# due-levelconverter.net
KiCad netlist of a schematic drawn in EAGLE
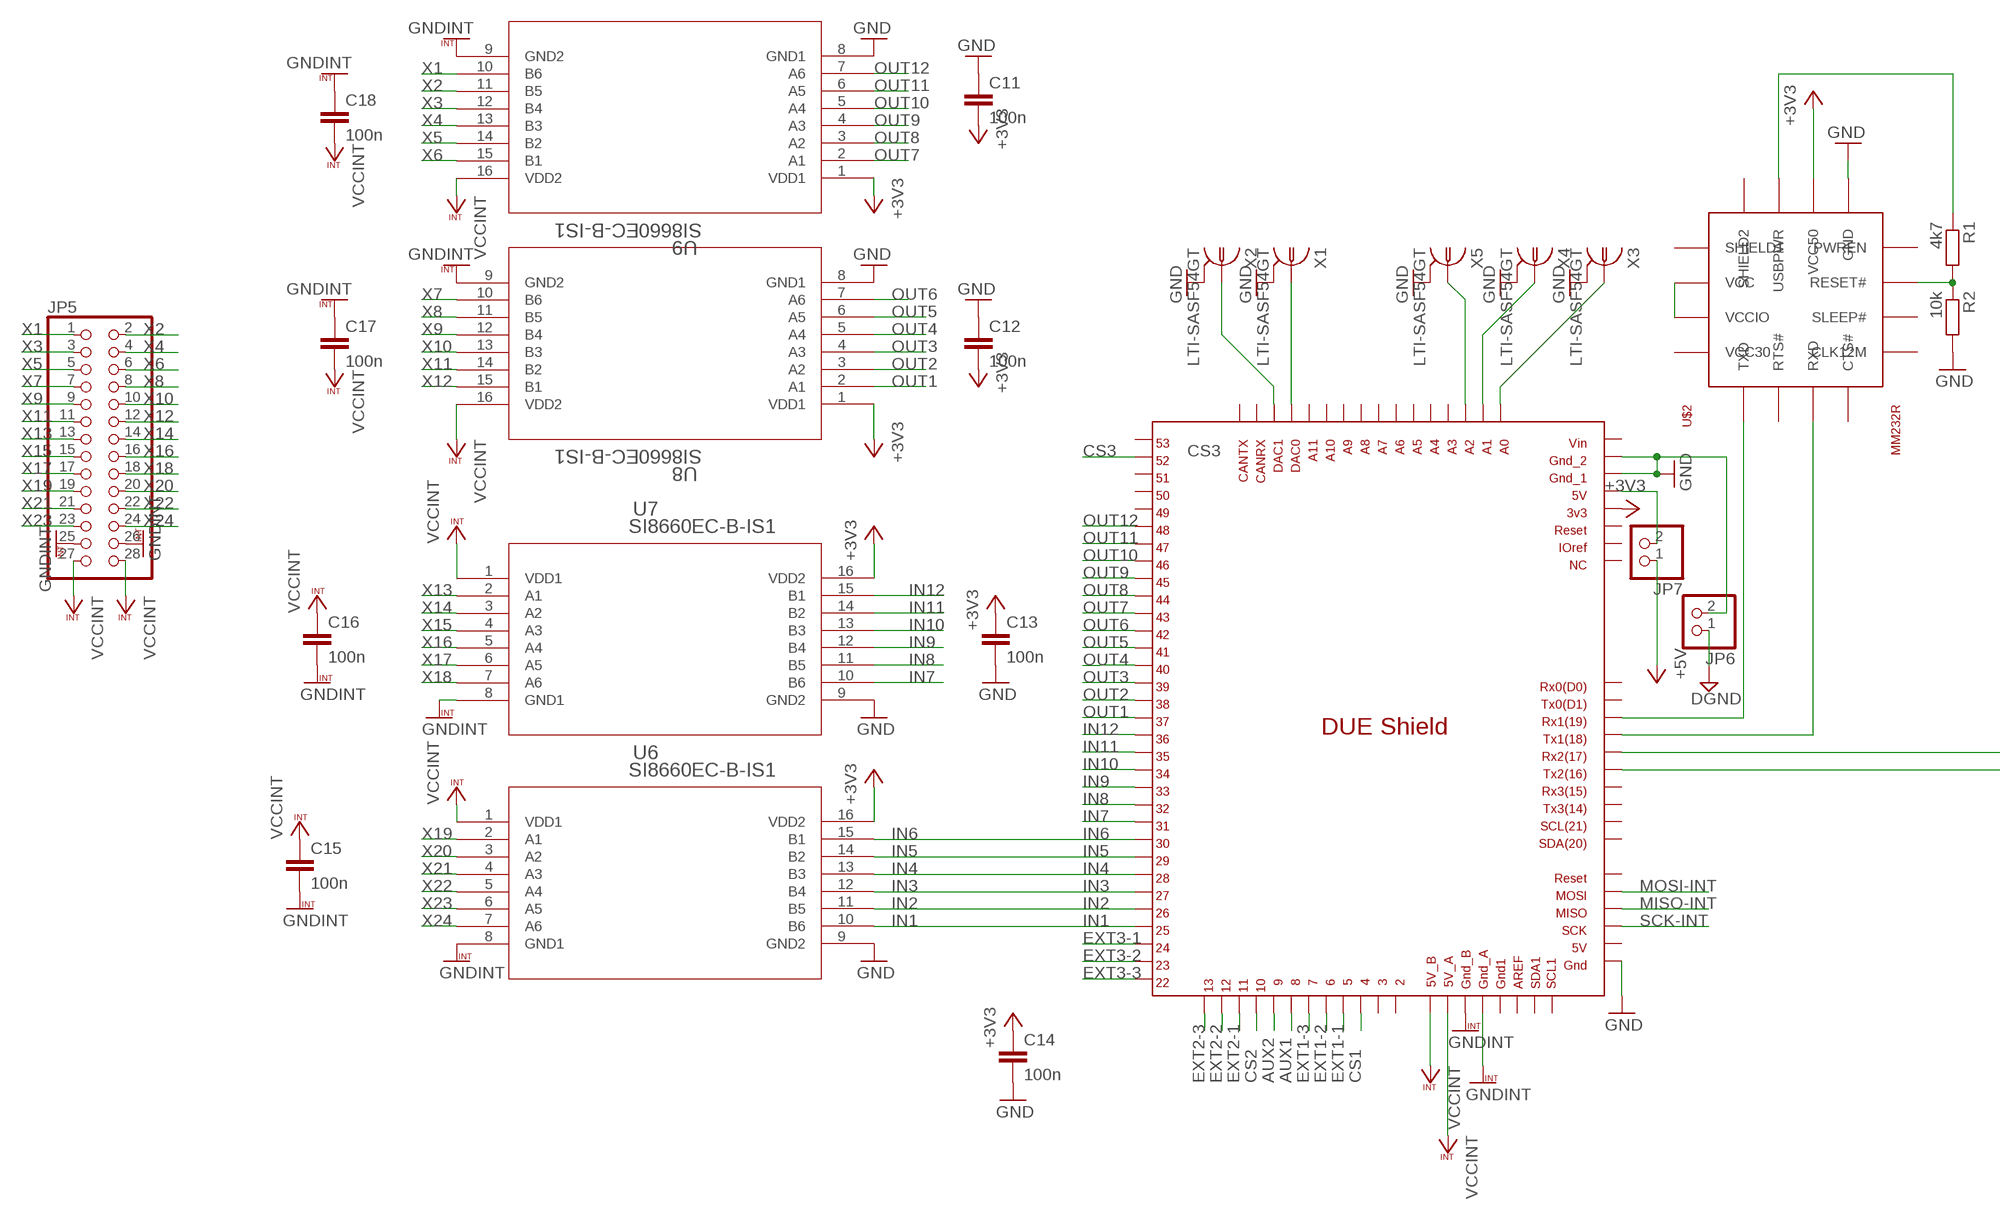
[diagram p0: schematic, sheet 1, part 1 of 2]
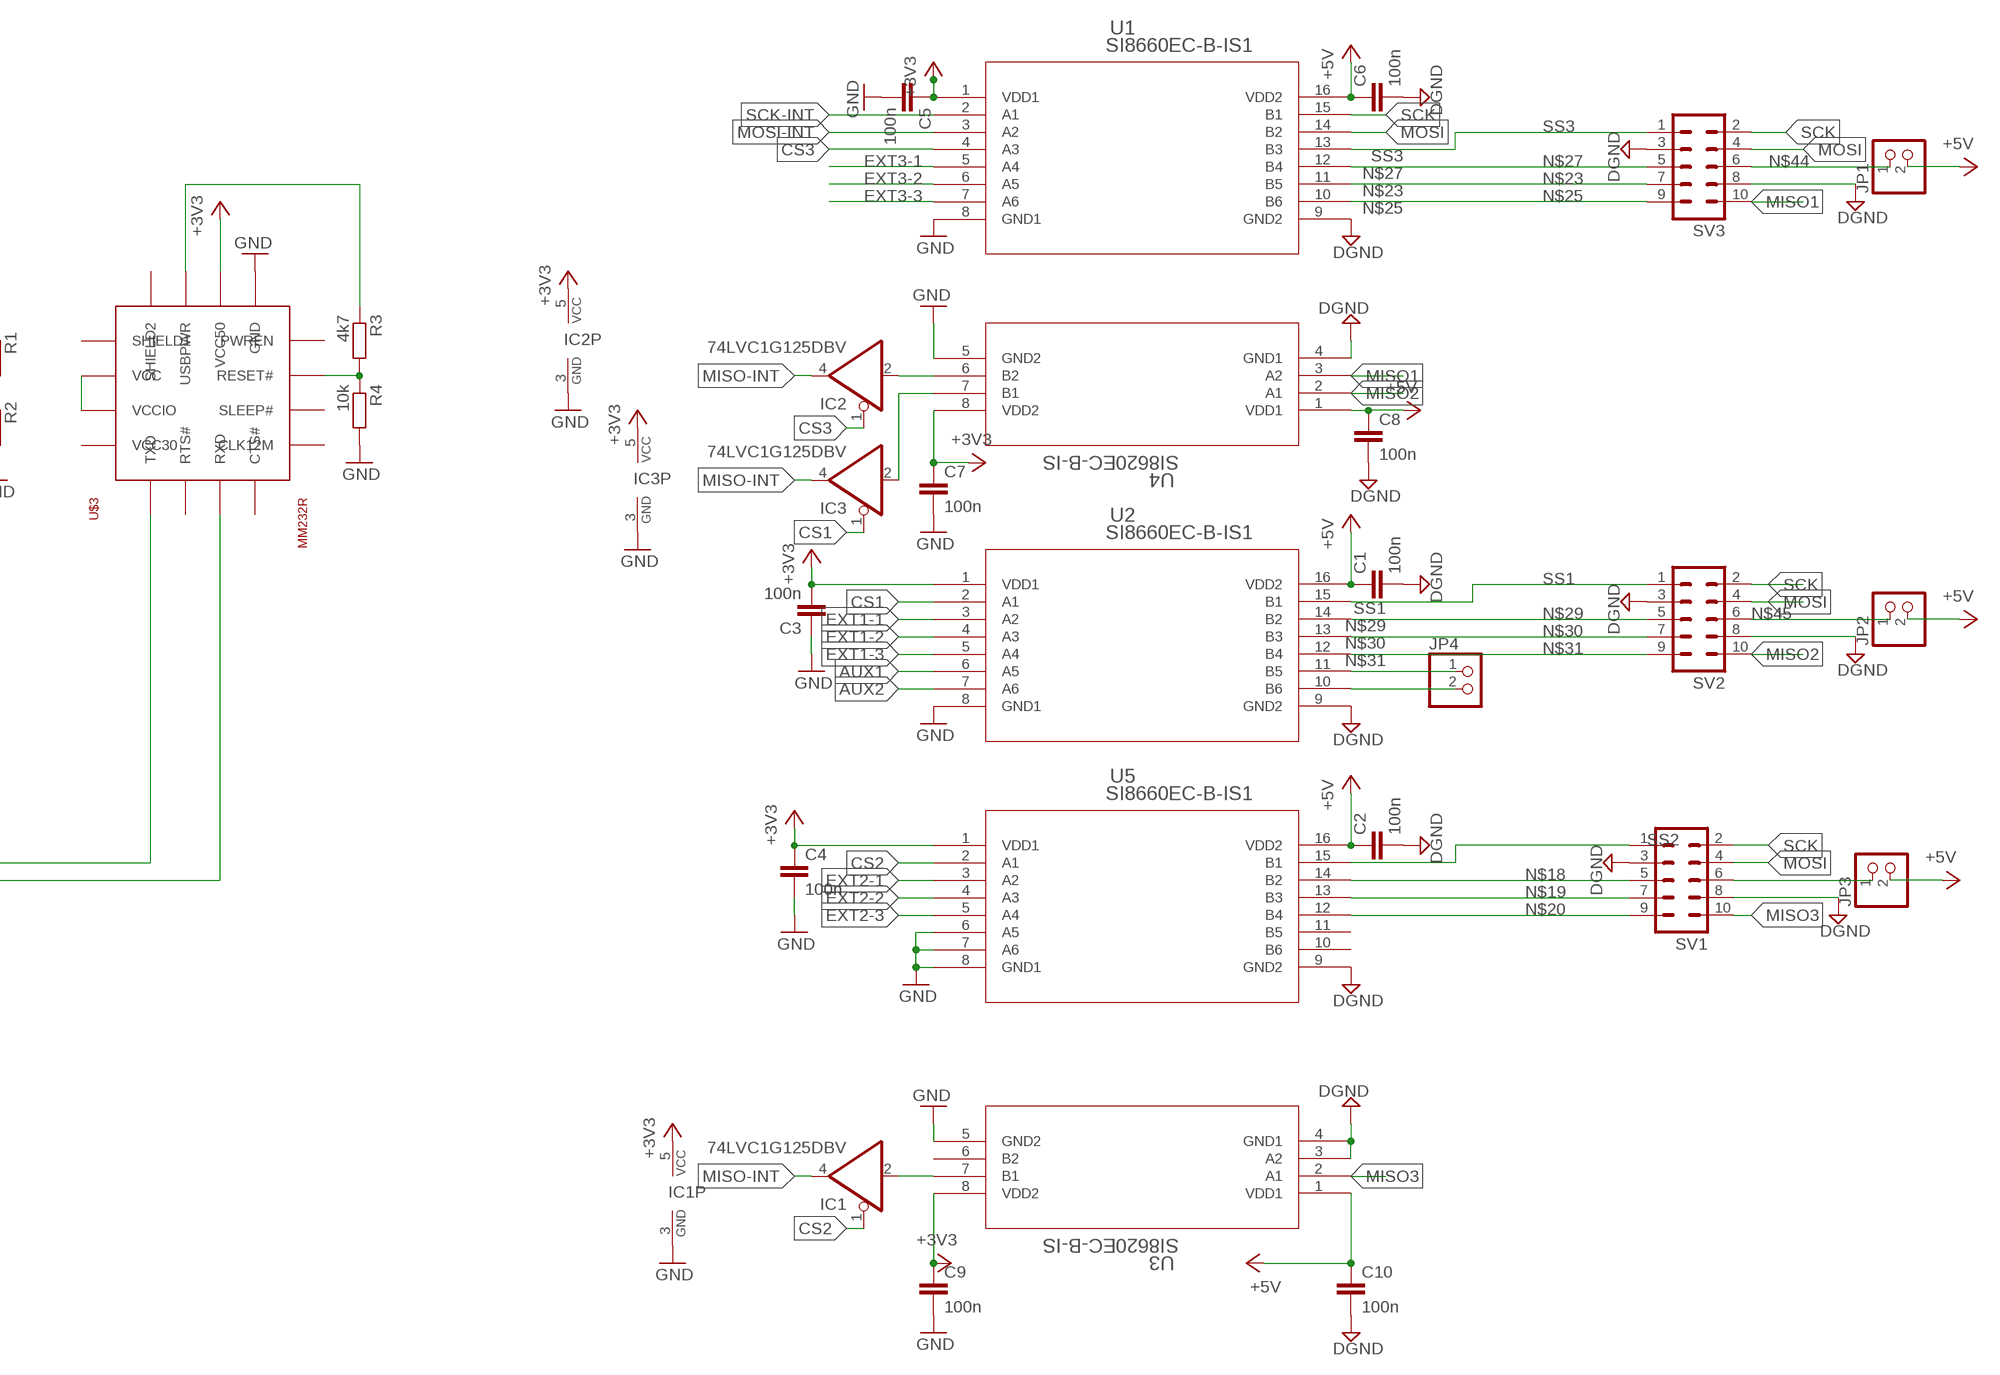
[diagram p1: schematic, sheet 1, part 2 of 2]

(export (version "E")
  (design (tool "Eeschema 10.0.6"))
  (components
    (comp (ref "C1")
      (value "100n")
      (footprint "eagle-import:C0805")
      (libsource (lib "eagle-import") (part "C-EUC0805"))
    )
    (comp (ref "C2")
      (value "100n")
      (footprint "eagle-import:C0805")
      (libsource (lib "eagle-import") (part "C-EUC0805"))
    )
    (comp (ref "C3")
      (value "100n")
      (footprint "eagle-import:C0805")
      (libsource (lib "eagle-import") (part "C-EUC0805"))
    )
    (comp (ref "C4")
      (value "100n")
      (footprint "eagle-import:C0805")
      (libsource (lib "eagle-import") (part "C-EUC0805"))
    )
    (comp (ref "C5")
      (value "100n")
      (footprint "eagle-import:C0805")
      (libsource (lib "eagle-import") (part "C-EUC0805"))
    )
    (comp (ref "C6")
      (value "100n")
      (footprint "eagle-import:C0805")
      (libsource (lib "eagle-import") (part "C-EUC0805"))
    )
    (comp (ref "C7")
      (value "100n")
      (footprint "eagle-import:C0805")
      (libsource (lib "eagle-import") (part "C-EUC0805"))
    )
    (comp (ref "C8")
      (value "100n")
      (footprint "eagle-import:C0805")
      (libsource (lib "eagle-import") (part "C-EUC0805"))
    )
    (comp (ref "C9")
      (value "100n")
      (footprint "eagle-import:C0805")
      (libsource (lib "eagle-import") (part "C-EUC0805"))
    )
    (comp (ref "C10")
      (value "100n")
      (footprint "eagle-import:C0805")
      (libsource (lib "eagle-import") (part "C-EUC0805"))
    )
    (comp (ref "C11")
      (value "100n")
      (footprint "eagle-import:C0805")
      (libsource (lib "eagle-import") (part "C-EUC0805"))
    )
    (comp (ref "C12")
      (value "100n")
      (footprint "eagle-import:C0805")
      (libsource (lib "eagle-import") (part "C-EUC0805"))
    )
    (comp (ref "C13")
      (value "100n")
      (footprint "eagle-import:C0805")
      (libsource (lib "eagle-import") (part "C-EUC0805"))
    )
    (comp (ref "C14")
      (value "100n")
      (footprint "eagle-import:C0805")
      (libsource (lib "eagle-import") (part "C-EUC0805"))
    )
    (comp (ref "C15")
      (value "100n")
      (footprint "eagle-import:C0805")
      (libsource (lib "eagle-import") (part "C-EUC0805"))
    )
    (comp (ref "C16")
      (value "100n")
      (footprint "eagle-import:C0805")
      (libsource (lib "eagle-import") (part "C-EUC0805"))
    )
    (comp (ref "C17")
      (value "100n")
      (footprint "eagle-import:C0805")
      (libsource (lib "eagle-import") (part "C-EUC0805"))
    )
    (comp (ref "C18")
      (value "100n")
      (footprint "eagle-import:C0805")
      (libsource (lib "eagle-import") (part "C-EUC0805"))
    )
    (comp (ref "IC1")
      (value "74LVC1G125DBV")
      (footprint "eagle-import:SOT23-5")
      (libsource (lib "eagle-import") (part "741G125DBVLVC"))
    )
    (comp (ref "IC2")
      (value "74LVC1G125DBV")
      (footprint "eagle-import:SOT23-5")
      (libsource (lib "eagle-import") (part "741G125DBVLVC"))
    )
    (comp (ref "IC3")
      (value "74LVC1G125DBV")
      (footprint "eagle-import:SOT23-5")
      (libsource (lib "eagle-import") (part "741G125DBVLVC"))
    )
    (comp (ref "JP1")
      (value "PINHD-1X2")
      (footprint "eagle-import:1X02")
      (libsource (lib "eagle-import") (part "PINHD-1X2"))
    )
    (comp (ref "JP2")
      (value "PINHD-1X2")
      (footprint "eagle-import:1X02")
      (libsource (lib "eagle-import") (part "PINHD-1X2"))
    )
    (comp (ref "JP3")
      (value "PINHD-1X2")
      (footprint "eagle-import:1X02")
      (libsource (lib "eagle-import") (part "PINHD-1X2"))
    )
    (comp (ref "JP4")
      (value "PINHD-1X2")
      (footprint "eagle-import:1X02")
      (libsource (lib "eagle-import") (part "PINHD-1X2"))
    )
    (comp (ref "JP5")
      (value "PINHD-2X14")
      (footprint "eagle-import:2X14")
      (libsource (lib "eagle-import") (part "PINHD-2X14"))
    )
    (comp (ref "JP6")
      (value "PINHD-1X2")
      (footprint "eagle-import:1X02")
      (libsource (lib "eagle-import") (part "PINHD-1X2"))
    )
    (comp (ref "JP7")
      (value "PINHD-1X2")
      (footprint "eagle-import:1X02")
      (libsource (lib "eagle-import") (part "PINHD-1X2"))
    )
    (comp (ref "R1")
      (value "4k7")
      (footprint "eagle-import:R0805")
      (libsource (lib "eagle-import") (part "R-EU_R0805"))
    )
    (comp (ref "R2")
      (value "10k")
      (footprint "eagle-import:R0805")
      (libsource (lib "eagle-import") (part "R-EU_R0805"))
    )
    (comp (ref "R3")
      (value "4k7")
      (footprint "eagle-import:R0805")
      (libsource (lib "eagle-import") (part "R-EU_R0805"))
    )
    (comp (ref "R4")
      (value "10k")
      (footprint "eagle-import:R0805")
      (libsource (lib "eagle-import") (part "R-EU_R0805"))
    )
    (comp (ref "SV1")
      (value "ML10")
      (footprint "eagle-import:ML10")
      (libsource (lib "eagle-import") (part "ML10"))
    )
    (comp (ref "SV2")
      (value "ML10")
      (footprint "eagle-import:ML10")
      (libsource (lib "eagle-import") (part "ML10"))
    )
    (comp (ref "SV3")
      (value "ML10")
      (footprint "eagle-import:ML10")
      (libsource (lib "eagle-import") (part "ML10"))
    )
    (comp (ref "U$1")
      (value "DUE(NORMAL)")
      (footprint "eagle-import:DUE(NORMAL)")
      (libsource (lib "eagle-import") (part "DUE(NORMAL)"))
    )
    (comp (ref "U$2")
      (value "MM232R")
      (footprint "eagle-import:MM232R")
      (libsource (lib "eagle-import") (part "MM232R"))
    )
    (comp (ref "U$3")
      (value "MM232R")
      (footprint "eagle-import:MM232R")
      (libsource (lib "eagle-import") (part "MM232R"))
    )
    (comp (ref "U1")
      (value "SI8660EC-B-IS1")
      (footprint "eagle-import:SOIC-16")
      (libsource (lib "eagle-import") (part "SI8660EC-B-IS1"))
    )
    (comp (ref "U2")
      (value "SI8660EC-B-IS1")
      (footprint "eagle-import:SOIC-16")
      (libsource (lib "eagle-import") (part "SI8660EC-B-IS1"))
    )
    (comp (ref "U3")
      (value "SI8620EC-B-IS")
      (footprint "eagle-import:SOIC-8")
      (libsource (lib "eagle-import") (part "SI8620EC-B-IS"))
    )
    (comp (ref "U4")
      (value "SI8620EC-B-IS")
      (footprint "eagle-import:SOIC-8")
      (libsource (lib "eagle-import") (part "SI8620EC-B-IS"))
    )
    (comp (ref "U5")
      (value "SI8660EC-B-IS1")
      (footprint "eagle-import:SOIC-16")
      (libsource (lib "eagle-import") (part "SI8660EC-B-IS1"))
    )
    (comp (ref "U6")
      (value "SI8660EC-B-IS1")
      (footprint "eagle-import:SOIC-16")
      (libsource (lib "eagle-import") (part "SI8660EC-B-IS1"))
    )
    (comp (ref "U7")
      (value "SI8660EC-B-IS1")
      (footprint "eagle-import:SOIC-16")
      (libsource (lib "eagle-import") (part "SI8660EC-B-IS1"))
    )
    (comp (ref "U8")
      (value "SI8660EC-B-IS1")
      (footprint "eagle-import:SOIC-16")
      (libsource (lib "eagle-import") (part "SI8660EC-B-IS1"))
    )
    (comp (ref "U9")
      (value "SI8660EC-B-IS1")
      (footprint "eagle-import:SOIC-16")
      (libsource (lib "eagle-import") (part "SI8660EC-B-IS1"))
    )
    (comp (ref "X1")
      (value "LTI-SASF54GT")
      (footprint "eagle-import:LTI-SASF54GT")
      (libsource (lib "eagle-import") (part "LTI-SASF54GT"))
    )
    (comp (ref "X2")
      (value "LTI-SASF54GT")
      (footprint "eagle-import:LTI-SASF54GT")
      (libsource (lib "eagle-import") (part "LTI-SASF54GT"))
    )
    (comp (ref "X3")
      (value "LTI-SASF54GT")
      (footprint "eagle-import:LTI-SASF54GT")
      (libsource (lib "eagle-import") (part "LTI-SASF54GT"))
    )
    (comp (ref "X4")
      (value "LTI-SASF54GT")
      (footprint "eagle-import:LTI-SASF54GT")
      (libsource (lib "eagle-import") (part "LTI-SASF54GT"))
    )
    (comp (ref "X5")
      (value "LTI-SASF54GT")
      (footprint "eagle-import:LTI-SASF54GT")
      (libsource (lib "eagle-import") (part "LTI-SASF54GT"))
    )
  )
  (nets
    (net (code "1") (name "+3V3") (class "Default")
      (node (ref "C11") (pin "2") (pinfunction "2_2") (pintype "passive"))
      (node (ref "C12") (pin "2") (pinfunction "2_2") (pintype "passive"))
      (node (ref "C13") (pin "1") (pinfunction "1_1") (pintype "passive"))
      (node (ref "C14") (pin "1") (pinfunction "1_1") (pintype "passive"))
      (node (ref "C3") (pin "2") (pinfunction "2_2") (pintype "passive"))
      (node (ref "C4") (pin "1") (pinfunction "1_1") (pintype "passive"))
      (node (ref "C5") (pin "1") (pinfunction "1_1") (pintype "passive"))
      (node (ref "C7") (pin "1") (pinfunction "1_1") (pintype "passive"))
      (node (ref "C9") (pin "1") (pinfunction "1_1") (pintype "passive"))
      (node (ref "IC1") (pin "5") (pinfunction "VCC_5") (pintype "power_in"))
      (node (ref "IC2") (pin "5") (pinfunction "VCC_5") (pintype "power_in"))
      (node (ref "IC3") (pin "5") (pinfunction "VCC_5") (pintype "power_in"))
      (node (ref "U$1") (pin "3V3") (pinfunction "3V3_3V3") (pintype "bidirectional"))
      (node (ref "U$2") (pin "P$14") (pinfunction "VCC50_P$14") (pintype "bidirectional"))
      (node (ref "U$3") (pin "P$14") (pinfunction "VCC50_P$14") (pintype "bidirectional"))
      (node (ref "U1") (pin "1") (pinfunction "VDD1_1") (pintype "passive"))
      (node (ref "U2") (pin "1") (pinfunction "VDD1_1") (pintype "passive"))
      (node (ref "U3") (pin "8") (pinfunction "VDD2_8") (pintype "passive"))
      (node (ref "U4") (pin "8") (pinfunction "VDD2_8") (pintype "passive"))
      (node (ref "U5") (pin "1") (pinfunction "VDD1_1") (pintype "passive"))
      (node (ref "U6") (pin "16") (pinfunction "VDD2_16") (pintype "passive"))
      (node (ref "U7") (pin "16") (pinfunction "VDD2_16") (pintype "passive"))
      (node (ref "U8") (pin "1") (pinfunction "VDD1_1") (pintype "passive"))
      (node (ref "U9") (pin "1") (pinfunction "VDD1_1") (pintype "passive"))
    )
    (net (code "2") (name "+5V") (class "Default")
      (node (ref "C1") (pin "1") (pinfunction "1_1") (pintype "passive"))
      (node (ref "C10") (pin "1") (pinfunction "1_1") (pintype "passive"))
      (node (ref "C2") (pin "1") (pinfunction "1_1") (pintype "passive"))
      (node (ref "C6") (pin "1") (pinfunction "1_1") (pintype "passive"))
      (node (ref "C8") (pin "1") (pinfunction "1_1") (pintype "passive"))
      (node (ref "JP1") (pin "2") (pinfunction "2_2") (pintype "passive"))
      (node (ref "JP2") (pin "2") (pinfunction "2_2") (pintype "passive"))
      (node (ref "JP3") (pin "2") (pinfunction "2_2") (pintype "passive"))
      (node (ref "JP7") (pin "1") (pinfunction "1_1") (pintype "passive"))
      (node (ref "U1") (pin "16") (pinfunction "VDD2_16") (pintype "passive"))
      (node (ref "U2") (pin "16") (pinfunction "VDD2_16") (pintype "passive"))
      (node (ref "U3") (pin "1") (pinfunction "VDD1_1") (pintype "passive"))
      (node (ref "U4") (pin "1") (pinfunction "VDD1_1") (pintype "passive"))
      (node (ref "U5") (pin "16") (pinfunction "VDD2_16") (pintype "passive"))
    )
    (net (code "3") (name "/EXT3-1") (class "Default")
      (node (ref "U$1") (pin "24") (pinfunction "24_24") (pintype "bidirectional"))
      (node (ref "U1") (pin "5") (pinfunction "A4_5") (pintype "input"))
    )
    (net (code "4") (name "/EXT3-2") (class "Default")
      (node (ref "U$1") (pin "23") (pinfunction "23_23") (pintype "bidirectional"))
      (node (ref "U1") (pin "6") (pinfunction "A5_6") (pintype "input"))
    )
    (net (code "5") (name "/EXT3-3") (class "Default")
      (node (ref "U$1") (pin "22") (pinfunction "22_22") (pintype "bidirectional"))
      (node (ref "U1") (pin "7") (pinfunction "A6_7") (pintype "input"))
    )
    (net (code "6") (name "/IN1") (class "Default")
      (node (ref "U$1") (pin "25") (pinfunction "25_25") (pintype "bidirectional"))
      (node (ref "U6") (pin "10") (pinfunction "B6_10") (pintype "output"))
    )
    (net (code "7") (name "/IN2") (class "Default")
      (node (ref "U$1") (pin "26") (pinfunction "26_26") (pintype "bidirectional"))
      (node (ref "U6") (pin "11") (pinfunction "B5_11") (pintype "output"))
    )
    (net (code "8") (name "/IN3") (class "Default")
      (node (ref "U$1") (pin "27") (pinfunction "27_27") (pintype "bidirectional"))
      (node (ref "U6") (pin "12") (pinfunction "B4_12") (pintype "output"))
    )
    (net (code "9") (name "/IN4") (class "Default")
      (node (ref "U$1") (pin "28") (pinfunction "28_28") (pintype "bidirectional"))
      (node (ref "U6") (pin "13") (pinfunction "B3_13") (pintype "output"))
    )
    (net (code "10") (name "/IN5") (class "Default")
      (node (ref "U$1") (pin "29") (pinfunction "29_29") (pintype "bidirectional"))
      (node (ref "U6") (pin "14") (pinfunction "B2_14") (pintype "output"))
    )
    (net (code "11") (name "/IN6") (class "Default")
      (node (ref "U$1") (pin "30") (pinfunction "30_30") (pintype "bidirectional"))
      (node (ref "U6") (pin "15") (pinfunction "B1_15") (pintype "output"))
    )
    (net (code "12") (name "/IN7") (class "Default")
      (node (ref "U$1") (pin "31") (pinfunction "31_31") (pintype "bidirectional"))
      (node (ref "U7") (pin "10") (pinfunction "B6_10") (pintype "output"))
    )
    (net (code "13") (name "/IN8") (class "Default")
      (node (ref "U$1") (pin "32") (pinfunction "32_32") (pintype "bidirectional"))
      (node (ref "U7") (pin "11") (pinfunction "B5_11") (pintype "output"))
    )
    (net (code "14") (name "/IN9") (class "Default")
      (node (ref "U$1") (pin "33") (pinfunction "33_33") (pintype "bidirectional"))
      (node (ref "U7") (pin "12") (pinfunction "B4_12") (pintype "output"))
    )
    (net (code "15") (name "/IN10") (class "Default")
      (node (ref "U$1") (pin "34") (pinfunction "34_34") (pintype "bidirectional"))
      (node (ref "U7") (pin "13") (pinfunction "B3_13") (pintype "output"))
    )
    (net (code "16") (name "/IN11") (class "Default")
      (node (ref "U$1") (pin "35") (pinfunction "35_35") (pintype "bidirectional"))
      (node (ref "U7") (pin "14") (pinfunction "B2_14") (pintype "output"))
    )
    (net (code "17") (name "/IN12") (class "Default")
      (node (ref "U$1") (pin "36") (pinfunction "36_36") (pintype "bidirectional"))
      (node (ref "U7") (pin "15") (pinfunction "B1_15") (pintype "output"))
    )
    (net (code "18") (name "/N$18") (class "Default")
      (node (ref "SV1") (pin "5") (pinfunction "5_5") (pintype "passive"))
      (node (ref "U5") (pin "14") (pinfunction "B2_14") (pintype "output"))
    )
    (net (code "19") (name "/N$19") (class "Default")
      (node (ref "SV1") (pin "7") (pinfunction "7_7") (pintype "passive"))
      (node (ref "U5") (pin "13") (pinfunction "B3_13") (pintype "output"))
    )
    (net (code "20") (name "/N$20") (class "Default")
      (node (ref "SV1") (pin "9") (pinfunction "9_9") (pintype "passive"))
      (node (ref "U5") (pin "12") (pinfunction "B4_12") (pintype "output"))
    )
    (net (code "21") (name "/N$23") (class "Default")
      (node (ref "SV3") (pin "7") (pinfunction "7_7") (pintype "passive"))
      (node (ref "U1") (pin "11") (pinfunction "B5_11") (pintype "output"))
    )
    (net (code "22") (name "/N$25") (class "Default")
      (node (ref "SV3") (pin "9") (pinfunction "9_9") (pintype "passive"))
      (node (ref "U1") (pin "10") (pinfunction "B6_10") (pintype "output"))
    )
    (net (code "23") (name "/N$27") (class "Default")
      (node (ref "SV3") (pin "5") (pinfunction "5_5") (pintype "passive"))
      (node (ref "U1") (pin "12") (pinfunction "B4_12") (pintype "output"))
    )
    (net (code "24") (name "/N$29") (class "Default")
      (node (ref "SV2") (pin "5") (pinfunction "5_5") (pintype "passive"))
      (node (ref "U2") (pin "14") (pinfunction "B2_14") (pintype "output"))
    )
    (net (code "25") (name "/N$30") (class "Default")
      (node (ref "SV2") (pin "7") (pinfunction "7_7") (pintype "passive"))
      (node (ref "U2") (pin "13") (pinfunction "B3_13") (pintype "output"))
    )
    (net (code "26") (name "/N$31") (class "Default")
      (node (ref "SV2") (pin "9") (pinfunction "9_9") (pintype "passive"))
      (node (ref "U2") (pin "12") (pinfunction "B4_12") (pintype "output"))
    )
    (net (code "27") (name "/N$44") (class "Default")
      (node (ref "JP1") (pin "1") (pinfunction "1_1") (pintype "passive"))
      (node (ref "SV3") (pin "6") (pinfunction "6_6") (pintype "passive"))
    )
    (net (code "28") (name "/N$45") (class "Default")
      (node (ref "JP2") (pin "1") (pinfunction "1_1") (pintype "passive"))
      (node (ref "SV2") (pin "6") (pinfunction "6_6") (pintype "passive"))
    )
    (net (code "29") (name "/OUT1") (class "Default")
      (node (ref "U$1") (pin "37") (pinfunction "37_37") (pintype "bidirectional"))
      (node (ref "U8") (pin "2") (pinfunction "A1_2") (pintype "input"))
    )
    (net (code "30") (name "/OUT2") (class "Default")
      (node (ref "U$1") (pin "38") (pinfunction "38_38") (pintype "bidirectional"))
      (node (ref "U8") (pin "3") (pinfunction "A2_3") (pintype "input"))
    )
    (net (code "31") (name "/OUT3") (class "Default")
      (node (ref "U$1") (pin "39") (pinfunction "39_39") (pintype "bidirectional"))
      (node (ref "U8") (pin "4") (pinfunction "A3_4") (pintype "input"))
    )
    (net (code "32") (name "/OUT4") (class "Default")
      (node (ref "U$1") (pin "40") (pinfunction "40_40") (pintype "bidirectional"))
      (node (ref "U8") (pin "5") (pinfunction "A4_5") (pintype "input"))
    )
    (net (code "33") (name "/OUT5") (class "Default")
      (node (ref "U$1") (pin "41") (pinfunction "41_41") (pintype "bidirectional"))
      (node (ref "U8") (pin "6") (pinfunction "A5_6") (pintype "input"))
    )
    (net (code "34") (name "/OUT6") (class "Default")
      (node (ref "U$1") (pin "42") (pinfunction "42_42") (pintype "bidirectional"))
      (node (ref "U8") (pin "7") (pinfunction "A6_7") (pintype "input"))
    )
    (net (code "35") (name "/OUT7") (class "Default")
      (node (ref "U$1") (pin "43") (pinfunction "43_43") (pintype "bidirectional"))
      (node (ref "U9") (pin "2") (pinfunction "A1_2") (pintype "input"))
    )
    (net (code "36") (name "/OUT8") (class "Default")
      (node (ref "U$1") (pin "44") (pinfunction "44_44") (pintype "bidirectional"))
      (node (ref "U9") (pin "3") (pinfunction "A2_3") (pintype "input"))
    )
    (net (code "37") (name "/OUT9") (class "Default")
      (node (ref "U$1") (pin "45") (pinfunction "45_45") (pintype "bidirectional"))
      (node (ref "U9") (pin "4") (pinfunction "A3_4") (pintype "input"))
    )
    (net (code "38") (name "/OUT10") (class "Default")
      (node (ref "U$1") (pin "46") (pinfunction "46_46") (pintype "bidirectional"))
      (node (ref "U9") (pin "5") (pinfunction "A4_5") (pintype "input"))
    )
    (net (code "39") (name "/OUT11") (class "Default")
      (node (ref "U$1") (pin "47") (pinfunction "47_47") (pintype "bidirectional"))
      (node (ref "U9") (pin "6") (pinfunction "A5_6") (pintype "input"))
    )
    (net (code "40") (name "/OUT12") (class "Default")
      (node (ref "U$1") (pin "48") (pinfunction "48_48") (pintype "bidirectional"))
      (node (ref "U9") (pin "7") (pinfunction "A6_7") (pintype "input"))
    )
    (net (code "41") (name "/SS1") (class "Default")
      (node (ref "SV2") (pin "1") (pinfunction "1_1") (pintype "passive"))
      (node (ref "U2") (pin "15") (pinfunction "B1_15") (pintype "output"))
    )
    (net (code "42") (name "/SS2") (class "Default")
      (node (ref "SV1") (pin "1") (pinfunction "1_1") (pintype "passive"))
      (node (ref "U5") (pin "15") (pinfunction "B1_15") (pintype "output"))
    )
    (net (code "43") (name "/SS3") (class "Default")
      (node (ref "SV3") (pin "1") (pinfunction "1_1") (pintype "passive"))
      (node (ref "U1") (pin "13") (pinfunction "B3_13") (pintype "output"))
    )
    (net (code "44") (name "/X1") (class "Default")
      (node (ref "JP5") (pin "1") (pinfunction "1_1") (pintype "passive"))
      (node (ref "U9") (pin "10") (pinfunction "B6_10") (pintype "output"))
    )
    (net (code "45") (name "/X2") (class "Default")
      (node (ref "JP5") (pin "2") (pinfunction "2_2") (pintype "passive"))
      (node (ref "U9") (pin "11") (pinfunction "B5_11") (pintype "output"))
    )
    (net (code "46") (name "/X3") (class "Default")
      (node (ref "JP5") (pin "3") (pinfunction "3_3") (pintype "passive"))
      (node (ref "U9") (pin "12") (pinfunction "B4_12") (pintype "output"))
    )
    (net (code "47") (name "/X4") (class "Default")
      (node (ref "JP5") (pin "4") (pinfunction "4_4") (pintype "passive"))
      (node (ref "U9") (pin "13") (pinfunction "B3_13") (pintype "output"))
    )
    (net (code "48") (name "/X5") (class "Default")
      (node (ref "JP5") (pin "5") (pinfunction "5_5") (pintype "passive"))
      (node (ref "U9") (pin "14") (pinfunction "B2_14") (pintype "output"))
    )
    (net (code "49") (name "/X6") (class "Default")
      (node (ref "JP5") (pin "6") (pinfunction "6_6") (pintype "passive"))
      (node (ref "U9") (pin "15") (pinfunction "B1_15") (pintype "output"))
    )
    (net (code "50") (name "/X7") (class "Default")
      (node (ref "JP5") (pin "7") (pinfunction "7_7") (pintype "passive"))
      (node (ref "U8") (pin "10") (pinfunction "B6_10") (pintype "output"))
    )
    (net (code "51") (name "/X8") (class "Default")
      (node (ref "JP5") (pin "8") (pinfunction "8_8") (pintype "passive"))
      (node (ref "U8") (pin "11") (pinfunction "B5_11") (pintype "output"))
    )
    (net (code "52") (name "/X9") (class "Default")
      (node (ref "JP5") (pin "9") (pinfunction "9_9") (pintype "passive"))
      (node (ref "U8") (pin "12") (pinfunction "B4_12") (pintype "output"))
    )
    (net (code "53") (name "/X10") (class "Default")
      (node (ref "JP5") (pin "10") (pinfunction "10_10") (pintype "passive"))
      (node (ref "U8") (pin "13") (pinfunction "B3_13") (pintype "output"))
    )
    (net (code "54") (name "/X11") (class "Default")
      (node (ref "JP5") (pin "11") (pinfunction "11_11") (pintype "passive"))
      (node (ref "U8") (pin "14") (pinfunction "B2_14") (pintype "output"))
    )
    (net (code "55") (name "/X12") (class "Default")
      (node (ref "JP5") (pin "12") (pinfunction "12_12") (pintype "passive"))
      (node (ref "U8") (pin "15") (pinfunction "B1_15") (pintype "output"))
    )
    (net (code "56") (name "/X13") (class "Default")
      (node (ref "JP5") (pin "13") (pinfunction "13_13") (pintype "passive"))
      (node (ref "U7") (pin "2") (pinfunction "A1_2") (pintype "input"))
    )
    (net (code "57") (name "/X14") (class "Default")
      (node (ref "JP5") (pin "14") (pinfunction "14_14") (pintype "passive"))
      (node (ref "U7") (pin "3") (pinfunction "A2_3") (pintype "input"))
    )
    (net (code "58") (name "/X15") (class "Default")
      (node (ref "JP5") (pin "15") (pinfunction "15_15") (pintype "passive"))
      (node (ref "U7") (pin "4") (pinfunction "A3_4") (pintype "input"))
    )
    (net (code "59") (name "/X16") (class "Default")
      (node (ref "JP5") (pin "16") (pinfunction "16_16") (pintype "passive"))
      (node (ref "U7") (pin "5") (pinfunction "A4_5") (pintype "input"))
    )
    (net (code "60") (name "/X17") (class "Default")
      (node (ref "JP5") (pin "17") (pinfunction "17_17") (pintype "passive"))
      (node (ref "U7") (pin "6") (pinfunction "A5_6") (pintype "input"))
    )
    (net (code "61") (name "/X18") (class "Default")
      (node (ref "JP5") (pin "18") (pinfunction "18_18") (pintype "passive"))
      (node (ref "U7") (pin "7") (pinfunction "A6_7") (pintype "input"))
    )
    (net (code "62") (name "/X19") (class "Default")
      (node (ref "JP5") (pin "19") (pinfunction "19_19") (pintype "passive"))
      (node (ref "U6") (pin "2") (pinfunction "A1_2") (pintype "input"))
    )
    (net (code "63") (name "/X20") (class "Default")
      (node (ref "JP5") (pin "20") (pinfunction "20_20") (pintype "passive"))
      (node (ref "U6") (pin "3") (pinfunction "A2_3") (pintype "input"))
    )
    (net (code "64") (name "/X21") (class "Default")
      (node (ref "JP5") (pin "21") (pinfunction "21_21") (pintype "passive"))
      (node (ref "U6") (pin "4") (pinfunction "A3_4") (pintype "input"))
    )
    (net (code "65") (name "/X22") (class "Default")
      (node (ref "JP5") (pin "22") (pinfunction "22_22") (pintype "passive"))
      (node (ref "U6") (pin "5") (pinfunction "A4_5") (pintype "input"))
    )
    (net (code "66") (name "/X23") (class "Default")
      (node (ref "JP5") (pin "23") (pinfunction "23_23") (pintype "passive"))
      (node (ref "U6") (pin "6") (pinfunction "A5_6") (pintype "input"))
    )
    (net (code "67") (name "/X24") (class "Default")
      (node (ref "JP5") (pin "24") (pinfunction "24_24") (pintype "passive"))
      (node (ref "U6") (pin "7") (pinfunction "A6_7") (pintype "input"))
    )
    (net (code "68") (name "AUX1") (class "Default")
      (node (ref "U$1") (pin "8") (pinfunction "8_8") (pintype "bidirectional"))
      (node (ref "U2") (pin "6") (pinfunction "A5_6") (pintype "input"))
    )
    (net (code "69") (name "AUX2") (class "Default")
      (node (ref "U$1") (pin "9") (pinfunction "9_9") (pintype "bidirectional"))
      (node (ref "U2") (pin "7") (pinfunction "A6_7") (pintype "input"))
    )
    (net (code "70") (name "CS1") (class "Default")
      (node (ref "IC3") (pin "1") (pinfunction "OE_1") (pintype "input"))
      (node (ref "U$1") (pin "4") (pinfunction "4_4") (pintype "bidirectional"))
      (node (ref "U2") (pin "2") (pinfunction "A1_2") (pintype "input"))
    )
    (net (code "71") (name "CS2") (class "Default")
      (node (ref "IC1") (pin "1") (pinfunction "OE_1") (pintype "input"))
      (node (ref "U$1") (pin "10") (pinfunction "10_10") (pintype "bidirectional"))
      (node (ref "U5") (pin "2") (pinfunction "A1_2") (pintype "input"))
    )
    (net (code "72") (name "CS3") (class "Default")
      (node (ref "IC2") (pin "1") (pinfunction "OE_1") (pintype "input"))
      (node (ref "U$1") (pin "52") (pinfunction "52_52") (pintype "bidirectional"))
      (node (ref "U1") (pin "4") (pinfunction "A3_4") (pintype "input"))
    )
    (net (code "73") (name "DGND") (class "Default")
      (node (ref "C1") (pin "2") (pinfunction "2_2") (pintype "passive"))
      (node (ref "C10") (pin "2") (pinfunction "2_2") (pintype "passive"))
      (node (ref "C2") (pin "2") (pinfunction "2_2") (pintype "passive"))
      (node (ref "C6") (pin "2") (pinfunction "2_2") (pintype "passive"))
      (node (ref "C8") (pin "2") (pinfunction "2_2") (pintype "passive"))
      (node (ref "JP6") (pin "1") (pinfunction "1_1") (pintype "passive"))
      (node (ref "SV1") (pin "3") (pinfunction "3_3") (pintype "passive"))
      (node (ref "SV1") (pin "8") (pinfunction "8_8") (pintype "passive"))
      (node (ref "SV2") (pin "3") (pinfunction "3_3") (pintype "passive"))
      (node (ref "SV2") (pin "8") (pinfunction "8_8") (pintype "passive"))
      (node (ref "SV3") (pin "3") (pinfunction "3_3") (pintype "passive"))
      (node (ref "SV3") (pin "8") (pinfunction "8_8") (pintype "passive"))
      (node (ref "U1") (pin "9") (pinfunction "GND2_9") (pintype "passive"))
      (node (ref "U2") (pin "9") (pinfunction "GND2_9") (pintype "passive"))
      (node (ref "U3") (pin "3") (pinfunction "A2_3") (pintype "input"))
      (node (ref "U3") (pin "4") (pinfunction "GND1_4") (pintype "passive"))
      (node (ref "U4") (pin "4") (pinfunction "GND1_4") (pintype "passive"))
      (node (ref "U5") (pin "9") (pinfunction "GND2_9") (pintype "passive"))
    )
    (net (code "74") (name "EXT1-1") (class "Default")
      (node (ref "U$1") (pin "5") (pinfunction "5_5") (pintype "bidirectional"))
      (node (ref "U2") (pin "3") (pinfunction "A2_3") (pintype "input"))
    )
    (net (code "75") (name "EXT1-2") (class "Default")
      (node (ref "U$1") (pin "6") (pinfunction "6_6") (pintype "bidirectional"))
      (node (ref "U2") (pin "4") (pinfunction "A3_4") (pintype "input"))
    )
    (net (code "76") (name "EXT1-3") (class "Default")
      (node (ref "U$1") (pin "7") (pinfunction "7_7") (pintype "bidirectional"))
      (node (ref "U2") (pin "5") (pinfunction "A4_5") (pintype "input"))
    )
    (net (code "77") (name "EXT2-1") (class "Default")
      (node (ref "U$1") (pin "11") (pinfunction "11_11") (pintype "bidirectional"))
      (node (ref "U5") (pin "3") (pinfunction "A2_3") (pintype "input"))
    )
    (net (code "78") (name "EXT2-2") (class "Default")
      (node (ref "U$1") (pin "12") (pinfunction "12_12") (pintype "bidirectional"))
      (node (ref "U5") (pin "4") (pinfunction "A3_4") (pintype "input"))
    )
    (net (code "79") (name "EXT2-3") (class "Default")
      (node (ref "U$1") (pin "13") (pinfunction "13_13") (pintype "bidirectional"))
      (node (ref "U5") (pin "5") (pinfunction "A4_5") (pintype "input"))
    )
    (net (code "80") (name "GND") (class "Default")
      (node (ref "C11") (pin "1") (pinfunction "1_1") (pintype "passive"))
      (node (ref "C12") (pin "1") (pinfunction "1_1") (pintype "passive"))
      (node (ref "C13") (pin "2") (pinfunction "2_2") (pintype "passive"))
      (node (ref "C14") (pin "2") (pinfunction "2_2") (pintype "passive"))
      (node (ref "C3") (pin "1") (pinfunction "1_1") (pintype "passive"))
      (node (ref "C4") (pin "2") (pinfunction "2_2") (pintype "passive"))
      (node (ref "C5") (pin "2") (pinfunction "2_2") (pintype "passive"))
      (node (ref "C7") (pin "2") (pinfunction "2_2") (pintype "passive"))
      (node (ref "C9") (pin "2") (pinfunction "2_2") (pintype "passive"))
      (node (ref "IC1") (pin "3") (pinfunction "GND_3") (pintype "power_in"))
      (node (ref "IC2") (pin "3") (pinfunction "GND_3") (pintype "power_in"))
      (node (ref "IC3") (pin "3") (pinfunction "GND_3") (pintype "power_in"))
      (node (ref "JP6") (pin "2") (pinfunction "2_2") (pintype "passive"))
      (node (ref "R2") (pin "2") (pinfunction "2_2") (pintype "passive"))
      (node (ref "R4") (pin "2") (pinfunction "2_2") (pintype "passive"))
      (node (ref "U$1") (pin "5V_ICSP") (pinfunction "5V_ICSP_5V_ICSP") (pintype "bidirectional"))
      (node (ref "U$1") (pin "GND_1") (pinfunction "GND_1_GND_1") (pintype "bidirectional"))
      (node (ref "U$1") (pin "GND_2") (pinfunction "GND_2_GND_2") (pintype "bidirectional"))
      (node (ref "U$2") (pin "P$13") (pinfunction "GND_P$13") (pintype "bidirectional"))
      (node (ref "U$3") (pin "P$13") (pinfunction "GND_P$13") (pintype "bidirectional"))
      (node (ref "U1") (pin "8") (pinfunction "GND1_8") (pintype "passive"))
      (node (ref "U2") (pin "8") (pinfunction "GND1_8") (pintype "passive"))
      (node (ref "U3") (pin "5") (pinfunction "GND2_5") (pintype "passive"))
      (node (ref "U4") (pin "5") (pinfunction "GND2_5") (pintype "passive"))
      (node (ref "U5") (pin "6") (pinfunction "A5_6") (pintype "input"))
      (node (ref "U5") (pin "7") (pinfunction "A6_7") (pintype "input"))
      (node (ref "U5") (pin "8") (pinfunction "GND1_8") (pintype "passive"))
      (node (ref "U6") (pin "9") (pinfunction "GND2_9") (pintype "passive"))
      (node (ref "U7") (pin "9") (pinfunction "GND2_9") (pintype "passive"))
      (node (ref "U8") (pin "8") (pinfunction "GND1_8") (pintype "passive"))
      (node (ref "U9") (pin "8") (pinfunction "GND1_8") (pintype "passive"))
      (node (ref "X1") (pin "2") (pinfunction "2_2") (pintype "passive"))
      (node (ref "X1") (pin "3") (pinfunction "2_3") (pintype "passive"))
      (node (ref "X1") (pin "4") (pinfunction "2_4") (pintype "passive"))
      (node (ref "X1") (pin "5") (pinfunction "2_5") (pintype "passive"))
      (node (ref "X2") (pin "2") (pinfunction "2_2") (pintype "passive"))
      (node (ref "X2") (pin "3") (pinfunction "2_3") (pintype "passive"))
      (node (ref "X2") (pin "4") (pinfunction "2_4") (pintype "passive"))
      (node (ref "X2") (pin "5") (pinfunction "2_5") (pintype "passive"))
      (node (ref "X3") (pin "2") (pinfunction "2_2") (pintype "passive"))
      (node (ref "X3") (pin "3") (pinfunction "2_3") (pintype "passive"))
      (node (ref "X3") (pin "4") (pinfunction "2_4") (pintype "passive"))
      (node (ref "X3") (pin "5") (pinfunction "2_5") (pintype "passive"))
      (node (ref "X4") (pin "2") (pinfunction "2_2") (pintype "passive"))
      (node (ref "X4") (pin "3") (pinfunction "2_3") (pintype "passive"))
      (node (ref "X4") (pin "4") (pinfunction "2_4") (pintype "passive"))
      (node (ref "X4") (pin "5") (pinfunction "2_5") (pintype "passive"))
      (node (ref "X5") (pin "2") (pinfunction "2_2") (pintype "passive"))
      (node (ref "X5") (pin "3") (pinfunction "2_3") (pintype "passive"))
      (node (ref "X5") (pin "4") (pinfunction "2_4") (pintype "passive"))
      (node (ref "X5") (pin "5") (pinfunction "2_5") (pintype "passive"))
    )
    (net (code "81") (name "GNDINT") (class "Default")
      (node (ref "C15") (pin "2") (pinfunction "2_2") (pintype "passive"))
      (node (ref "C16") (pin "2") (pinfunction "2_2") (pintype "passive"))
      (node (ref "C17") (pin "1") (pinfunction "1_1") (pintype "passive"))
      (node (ref "C18") (pin "1") (pinfunction "1_1") (pintype "passive"))
      (node (ref "JP5") (pin "25") (pinfunction "25_25") (pintype "passive"))
      (node (ref "JP5") (pin "26") (pinfunction "26_26") (pintype "passive"))
      (node (ref "U$1") (pin "GND_A") (pinfunction "GND_A_GND_A") (pintype "bidirectional"))
      (node (ref "U$1") (pin "GND_B") (pinfunction "GND_B_GND_B") (pintype "bidirectional"))
      (node (ref "U6") (pin "8") (pinfunction "GND1_8") (pintype "passive"))
      (node (ref "U7") (pin "8") (pinfunction "GND1_8") (pintype "passive"))
      (node (ref "U8") (pin "9") (pinfunction "GND2_9") (pintype "passive"))
      (node (ref "U9") (pin "9") (pinfunction "GND2_9") (pintype "passive"))
    )
    (net (code "82") (name "MISO-INT") (class "Default")
      (node (ref "IC1") (pin "4") (pinfunction "O_4") (pintype "tri_state"))
      (node (ref "IC2") (pin "4") (pinfunction "O_4") (pintype "tri_state"))
      (node (ref "IC3") (pin "4") (pinfunction "O_4") (pintype "tri_state"))
      (node (ref "U$1") (pin "MISO_ICSP") (pinfunction "MISO_ICSP_MISO_ICSP") (pintype "bidirectional"))
    )
    (net (code "83") (name "MISO1") (class "Default")
      (node (ref "SV3") (pin "10") (pinfunction "10_10") (pintype "passive"))
      (node (ref "U4") (pin "3") (pinfunction "A2_3") (pintype "input"))
    )
    (net (code "84") (name "MISO2") (class "Default")
      (node (ref "SV2") (pin "10") (pinfunction "10_10") (pintype "passive"))
      (node (ref "U4") (pin "2") (pinfunction "A1_2") (pintype "input"))
    )
    (net (code "85") (name "MISO3") (class "Default")
      (node (ref "SV1") (pin "10") (pinfunction "10_10") (pintype "passive"))
      (node (ref "U3") (pin "2") (pinfunction "A1_2") (pintype "input"))
    )
    (net (code "86") (name "MOSI") (class "Default")
      (node (ref "SV1") (pin "4") (pinfunction "4_4") (pintype "passive"))
      (node (ref "SV2") (pin "4") (pinfunction "4_4") (pintype "passive"))
      (node (ref "SV3") (pin "4") (pinfunction "4_4") (pintype "passive"))
      (node (ref "U1") (pin "14") (pinfunction "B2_14") (pintype "output"))
    )
    (net (code "87") (name "MOSI-INT") (class "Default")
      (node (ref "U$1") (pin "MOSI_ICSP") (pinfunction "MOSI_ICSP_MOSI_ICSP") (pintype "bidirectional"))
      (node (ref "U1") (pin "3") (pinfunction "A2_3") (pintype "input"))
    )
    (net (code "88") (name "Net-(IC1A-I)") (class "Default")
      (node (ref "IC1") (pin "2") (pinfunction "I_2") (pintype "input"))
      (node (ref "U3") (pin "7") (pinfunction "B1_7") (pintype "output"))
    )
    (net (code "89") (name "Net-(IC2A-I)") (class "Default")
      (node (ref "IC2") (pin "2") (pinfunction "I_2") (pintype "input"))
      (node (ref "U4") (pin "6") (pinfunction "B2_6") (pintype "output"))
    )
    (net (code "90") (name "Net-(IC3A-I)") (class "Default")
      (node (ref "IC3") (pin "2") (pinfunction "I_2") (pintype "input"))
      (node (ref "U4") (pin "7") (pinfunction "B1_7") (pintype "output"))
    )
    (net (code "91") (name "Net-(JP3-Pad1)") (class "Default")
      (node (ref "JP3") (pin "1") (pinfunction "1_1") (pintype "passive"))
      (node (ref "SV1") (pin "6") (pinfunction "6_6") (pintype "passive"))
    )
    (net (code "92") (name "Net-(JP7-Pad2)") (class "Default")
      (node (ref "JP7") (pin "2") (pinfunction "2_2") (pintype "passive"))
      (node (ref "U$1") (pin "5V") (pinfunction "5V_5V") (pintype "bidirectional"))
    )
    (net (code "93") (name "Net-(U$1-PadA0)") (class "Default")
      (node (ref "U$1") (pin "A0") (pinfunction "A0_A0") (pintype "bidirectional"))
      (node (ref "X3") (pin "1") (pinfunction "1_1") (pintype "passive"))
    )
    (net (code "94") (name "Net-(U$1-PadA1)") (class "Default")
      (node (ref "U$1") (pin "A1") (pinfunction "A1_A1") (pintype "bidirectional"))
      (node (ref "X4") (pin "1") (pinfunction "1_1") (pintype "passive"))
    )
    (net (code "95") (name "Net-(U$1-PadA2)") (class "Default")
      (node (ref "U$1") (pin "A2") (pinfunction "A2_A2") (pintype "bidirectional"))
      (node (ref "X5") (pin "1") (pinfunction "1_1") (pintype "passive"))
    )
    (net (code "96") (name "Net-(U$1-PadDAC0)") (class "Default")
      (node (ref "U$1") (pin "DAC0") (pinfunction "DAC0_DAC0") (pintype "bidirectional"))
      (node (ref "X1") (pin "1") (pinfunction "1_1") (pintype "passive"))
    )
    (net (code "97") (name "Net-(U$1-PadDAC1)") (class "Default")
      (node (ref "U$1") (pin "DAC1") (pinfunction "DAC1_DAC1") (pintype "bidirectional"))
      (node (ref "X2") (pin "1") (pinfunction "1_1") (pintype "passive"))
    )
    (net (code "98") (name "Net-(U$2-RESET#)") (class "Default")
      (node (ref "R1") (pin "2") (pinfunction "2_2") (pintype "passive"))
      (node (ref "R2") (pin "1") (pinfunction "1_1") (pintype "passive"))
      (node (ref "U$2") (pin "P$11") (pinfunction "RESET#_P$11") (pintype "bidirectional"))
    )
    (net (code "99") (name "Net-(U$2-RXD)") (class "Default")
      (node (ref "U$1") (pin "TX1") (pinfunction "TX1_TX1") (pintype "bidirectional"))
      (node (ref "U$2") (pin "P$7") (pinfunction "RXD_P$7") (pintype "bidirectional"))
    )
    (net (code "100") (name "Net-(U$2-TXD)") (class "Default")
      (node (ref "U$1") (pin "RX1") (pinfunction "RX1_RX1") (pintype "bidirectional"))
      (node (ref "U$2") (pin "P$5") (pinfunction "TXD_P$5") (pintype "bidirectional"))
    )
    (net (code "101") (name "Net-(U$2-USBPWR)") (class "Default")
      (node (ref "R1") (pin "1") (pinfunction "1_1") (pintype "passive"))
      (node (ref "U$2") (pin "P$15") (pinfunction "USBPWR_P$15") (pintype "bidirectional"))
    )
    (net (code "102") (name "Net-(U$2-VCC)") (class "Default")
      (node (ref "U$2") (pin "P$2") (pinfunction "VCC_P$2") (pintype "bidirectional"))
      (node (ref "U$2") (pin "P$3") (pinfunction "VCCIO_P$3") (pintype "bidirectional"))
    )
    (net (code "103") (name "Net-(U$3-RESET#)") (class "Default")
      (node (ref "R3") (pin "2") (pinfunction "2_2") (pintype "passive"))
      (node (ref "R4") (pin "1") (pinfunction "1_1") (pintype "passive"))
      (node (ref "U$3") (pin "P$11") (pinfunction "RESET#_P$11") (pintype "bidirectional"))
    )
    (net (code "104") (name "Net-(U$3-RXD)") (class "Default")
      (node (ref "U$1") (pin "TX2") (pinfunction "TX2_TX2") (pintype "bidirectional"))
      (node (ref "U$3") (pin "P$7") (pinfunction "RXD_P$7") (pintype "bidirectional"))
    )
    (net (code "105") (name "Net-(U$3-TXD)") (class "Default")
      (node (ref "U$1") (pin "RX2") (pinfunction "RX2_RX2") (pintype "bidirectional"))
      (node (ref "U$3") (pin "P$5") (pinfunction "TXD_P$5") (pintype "bidirectional"))
    )
    (net (code "106") (name "Net-(U$3-USBPWR)") (class "Default")
      (node (ref "R3") (pin "1") (pinfunction "1_1") (pintype "passive"))
      (node (ref "U$3") (pin "P$15") (pinfunction "USBPWR_P$15") (pintype "bidirectional"))
    )
    (net (code "107") (name "Net-(U$3-VCC)") (class "Default")
      (node (ref "U$3") (pin "P$2") (pinfunction "VCC_P$2") (pintype "bidirectional"))
      (node (ref "U$3") (pin "P$3") (pinfunction "VCCIO_P$3") (pintype "bidirectional"))
    )
    (net (code "108") (name "Net-(U2-B5)") (class "Default")
      (node (ref "JP4") (pin "1") (pinfunction "1_1") (pintype "passive"))
      (node (ref "U2") (pin "11") (pinfunction "B5_11") (pintype "output"))
    )
    (net (code "109") (name "Net-(U2-B6)") (class "Default")
      (node (ref "JP4") (pin "2") (pinfunction "2_2") (pintype "passive"))
      (node (ref "U2") (pin "10") (pinfunction "B6_10") (pintype "output"))
    )
    (net (code "110") (name "SCK") (class "Default")
      (node (ref "SV1") (pin "2") (pinfunction "2_2") (pintype "passive"))
      (node (ref "SV2") (pin "2") (pinfunction "2_2") (pintype "passive"))
      (node (ref "SV3") (pin "2") (pinfunction "2_2") (pintype "passive"))
      (node (ref "U1") (pin "15") (pinfunction "B1_15") (pintype "output"))
    )
    (net (code "111") (name "SCK-INT") (class "Default")
      (node (ref "U$1") (pin "SCK_ICSP") (pinfunction "SCK_ICSP_SCK_ICSP") (pintype "bidirectional"))
      (node (ref "U1") (pin "2") (pinfunction "A1_2") (pintype "input"))
    )
    (net (code "112") (name "VCCINT") (class "Default")
      (node (ref "C15") (pin "1") (pinfunction "1_1") (pintype "passive"))
      (node (ref "C16") (pin "1") (pinfunction "1_1") (pintype "passive"))
      (node (ref "C17") (pin "2") (pinfunction "2_2") (pintype "passive"))
      (node (ref "C18") (pin "2") (pinfunction "2_2") (pintype "passive"))
      (node (ref "JP5") (pin "27") (pinfunction "27_27") (pintype "passive"))
      (node (ref "JP5") (pin "28") (pinfunction "28_28") (pintype "passive"))
      (node (ref "U$1") (pin "5V_A") (pinfunction "5V_A_5V_A") (pintype "bidirectional"))
      (node (ref "U$1") (pin "5V_B") (pinfunction "5V_B_5V_B") (pintype "bidirectional"))
      (node (ref "U6") (pin "1") (pinfunction "VDD1_1") (pintype "passive"))
      (node (ref "U7") (pin "1") (pinfunction "VDD1_1") (pintype "passive"))
      (node (ref "U8") (pin "16") (pinfunction "VDD2_16") (pintype "passive"))
      (node (ref "U9") (pin "16") (pinfunction "VDD2_16") (pintype "passive"))
    )
    (net (code "113") (name "unconnected-(U$1-Pad2)") (class "Default")
      (node (ref "U$1") (pin "2") (pinfunction "2_2") (pintype "bidirectional"))
    )
    (net (code "114") (name "unconnected-(U$1-Pad3)") (class "Default")
      (node (ref "U$1") (pin "3") (pinfunction "3_3") (pintype "bidirectional"))
    )
    (net (code "115") (name "unconnected-(U$1-Pad49)") (class "Default")
      (node (ref "U$1") (pin "49") (pinfunction "49_49") (pintype "bidirectional"))
    )
    (net (code "116") (name "unconnected-(U$1-Pad50)") (class "Default")
      (node (ref "U$1") (pin "50") (pinfunction "50_50") (pintype "bidirectional"))
    )
    (net (code "117") (name "unconnected-(U$1-Pad51)") (class "Default")
      (node (ref "U$1") (pin "51") (pinfunction "51_51") (pintype "bidirectional"))
    )
    (net (code "118") (name "unconnected-(U$1-Pad53)") (class "Default")
      (node (ref "U$1") (pin "53") (pinfunction "53_53") (pintype "bidirectional"))
    )
    (net (code "119") (name "unconnected-(U$1-PadA3)") (class "Default")
      (node (ref "U$1") (pin "A3") (pinfunction "A3_A3") (pintype "bidirectional"))
    )
    (net (code "120") (name "unconnected-(U$1-PadA4)") (class "Default")
      (node (ref "U$1") (pin "A4") (pinfunction "A4_A4") (pintype "bidirectional"))
    )
    (net (code "121") (name "unconnected-(U$1-PadA5)") (class "Default")
      (node (ref "U$1") (pin "A5") (pinfunction "A5_A5") (pintype "bidirectional"))
    )
    (net (code "122") (name "unconnected-(U$1-PadA6)") (class "Default")
      (node (ref "U$1") (pin "A6") (pinfunction "A6_A6") (pintype "bidirectional"))
    )
    (net (code "123") (name "unconnected-(U$1-PadA7)") (class "Default")
      (node (ref "U$1") (pin "A7") (pinfunction "A7_A7") (pintype "bidirectional"))
    )
    (net (code "124") (name "unconnected-(U$1-PadA8)") (class "Default")
      (node (ref "U$1") (pin "A8") (pinfunction "A8_A8") (pintype "bidirectional"))
    )
    (net (code "125") (name "unconnected-(U$1-PadA9)") (class "Default")
      (node (ref "U$1") (pin "A9") (pinfunction "A9_A9") (pintype "bidirectional"))
    )
    (net (code "126") (name "unconnected-(U$1-PadA10)") (class "Default")
      (node (ref "U$1") (pin "A10") (pinfunction "A10_A10") (pintype "bidirectional"))
    )
    (net (code "127") (name "unconnected-(U$1-PadA11)") (class "Default")
      (node (ref "U$1") (pin "A11") (pinfunction "A11_A11") (pintype "bidirectional"))
    )
    (net (code "128") (name "unconnected-(U$1-PadAREF)") (class "Default")
      (node (ref "U$1") (pin "AREF") (pinfunction "AREF_AREF") (pintype "bidirectional"))
    )
    (net (code "129") (name "unconnected-(U$1-PadCANRX)") (class "Default")
      (node (ref "U$1") (pin "CANRX") (pinfunction "CANRX_CANRX") (pintype "bidirectional"))
    )
    (net (code "130") (name "unconnected-(U$1-PadCANTX)") (class "Default")
      (node (ref "U$1") (pin "CANTX") (pinfunction "CANTX_CANTX") (pintype "bidirectional"))
    )
    (net (code "131") (name "unconnected-(U$1-PadGND1)") (class "Default")
      (node (ref "U$1") (pin "GND1") (pinfunction "GND1_GND1") (pintype "bidirectional"))
    )
    (net (code "132") (name "unconnected-(U$1-PadGND_ICSP)") (class "Default")
      (node (ref "U$1") (pin "GND_ICSP") (pinfunction "GND_ICSP_GND_ICSP") (pintype "bidirectional"))
    )
    (net (code "133") (name "unconnected-(U$1-PadIOREF)") (class "Default")
      (node (ref "U$1") (pin "IOREF") (pinfunction "IOREF_IOREF") (pintype "bidirectional"))
    )
    (net (code "134") (name "unconnected-(U$1-PadNC)") (class "Default")
      (node (ref "U$1") (pin "NC") (pinfunction "NC_NC") (pintype "bidirectional"))
    )
    (net (code "135") (name "unconnected-(U$1-PadRESET)") (class "Default")
      (node (ref "U$1") (pin "RESET") (pinfunction "RESET_RESET") (pintype "bidirectional"))
    )
    (net (code "136") (name "unconnected-(U$1-PadRESET_ICSP)") (class "Default")
      (node (ref "U$1") (pin "RESET_ICSP") (pinfunction "RESET_ICSP_RESET_ICSP") (pintype "bidirectional"))
    )
    (net (code "137") (name "unconnected-(U$1-PadRX0)") (class "Default")
      (node (ref "U$1") (pin "RX0") (pinfunction "RX0_RX0") (pintype "bidirectional"))
    )
    (net (code "138") (name "unconnected-(U$1-PadRX3)") (class "Default")
      (node (ref "U$1") (pin "RX3") (pinfunction "RX3_RX3") (pintype "bidirectional"))
    )
    (net (code "139") (name "unconnected-(U$1-PadSCL)") (class "Default")
      (node (ref "U$1") (pin "SCL") (pinfunction "SCL_SCL") (pintype "bidirectional"))
    )
    (net (code "140") (name "unconnected-(U$1-PadSCL1)") (class "Default")
      (node (ref "U$1") (pin "SCL1") (pinfunction "SCL1_SCL1") (pintype "bidirectional"))
    )
    (net (code "141") (name "unconnected-(U$1-PadSDA)") (class "Default")
      (node (ref "U$1") (pin "SDA") (pinfunction "SDA_SDA") (pintype "bidirectional"))
    )
    (net (code "142") (name "unconnected-(U$1-PadSDA1)") (class "Default")
      (node (ref "U$1") (pin "SDA1") (pinfunction "SDA1_SDA1") (pintype "bidirectional"))
    )
    (net (code "143") (name "unconnected-(U$1-PadTX0)") (class "Default")
      (node (ref "U$1") (pin "TX0") (pinfunction "TX0_TX0") (pintype "bidirectional"))
    )
    (net (code "144") (name "unconnected-(U$1-PadTX3)") (class "Default")
      (node (ref "U$1") (pin "TX3") (pinfunction "TX3_TX3") (pintype "bidirectional"))
    )
    (net (code "145") (name "unconnected-(U$1-PadVIN)") (class "Default")
      (node (ref "U$1") (pin "VIN") (pinfunction "VIN_VIN") (pintype "bidirectional"))
    )
    (net (code "146") (name "unconnected-(U$2-CLK12M-PadP$9)") (class "Default")
      (node (ref "U$2") (pin "P$9") (pinfunction "CLK12M_P$9") (pintype "bidirectional"))
    )
    (net (code "147") (name "unconnected-(U$2-CTS#-PadP$8)") (class "Default")
      (node (ref "U$2") (pin "P$8") (pinfunction "CTS#_P$8") (pintype "bidirectional"))
    )
    (net (code "148") (name "unconnected-(U$2-PWREN-PadP$12)") (class "Default")
      (node (ref "U$2") (pin "P$12") (pinfunction "PWREN_P$12") (pintype "bidirectional"))
    )
    (net (code "149") (name "unconnected-(U$2-RTS#-PadP$6)") (class "Default")
      (node (ref "U$2") (pin "P$6") (pinfunction "RTS#_P$6") (pintype "bidirectional"))
    )
    (net (code "150") (name "unconnected-(U$2-SHIELD1-PadP$1)") (class "Default")
      (node (ref "U$2") (pin "P$1") (pinfunction "SHIELD1_P$1") (pintype "bidirectional"))
    )
    (net (code "151") (name "unconnected-(U$2-SHIELD2-PadP$16)") (class "Default")
      (node (ref "U$2") (pin "P$16") (pinfunction "SHIELD2_P$16") (pintype "bidirectional"))
    )
    (net (code "152") (name "unconnected-(U$2-SLEEP#-PadP$10)") (class "Default")
      (node (ref "U$2") (pin "P$10") (pinfunction "SLEEP#_P$10") (pintype "bidirectional"))
    )
    (net (code "153") (name "unconnected-(U$2-VCC30-PadP$4)") (class "Default")
      (node (ref "U$2") (pin "P$4") (pinfunction "VCC30_P$4") (pintype "bidirectional"))
    )
    (net (code "154") (name "unconnected-(U$3-CLK12M-PadP$9)") (class "Default")
      (node (ref "U$3") (pin "P$9") (pinfunction "CLK12M_P$9") (pintype "bidirectional"))
    )
    (net (code "155") (name "unconnected-(U$3-CTS#-PadP$8)") (class "Default")
      (node (ref "U$3") (pin "P$8") (pinfunction "CTS#_P$8") (pintype "bidirectional"))
    )
    (net (code "156") (name "unconnected-(U$3-PWREN-PadP$12)") (class "Default")
      (node (ref "U$3") (pin "P$12") (pinfunction "PWREN_P$12") (pintype "bidirectional"))
    )
    (net (code "157") (name "unconnected-(U$3-RTS#-PadP$6)") (class "Default")
      (node (ref "U$3") (pin "P$6") (pinfunction "RTS#_P$6") (pintype "bidirectional"))
    )
    (net (code "158") (name "unconnected-(U$3-SHIELD1-PadP$1)") (class "Default")
      (node (ref "U$3") (pin "P$1") (pinfunction "SHIELD1_P$1") (pintype "bidirectional"))
    )
    (net (code "159") (name "unconnected-(U$3-SHIELD2-PadP$16)") (class "Default")
      (node (ref "U$3") (pin "P$16") (pinfunction "SHIELD2_P$16") (pintype "bidirectional"))
    )
    (net (code "160") (name "unconnected-(U$3-SLEEP#-PadP$10)") (class "Default")
      (node (ref "U$3") (pin "P$10") (pinfunction "SLEEP#_P$10") (pintype "bidirectional"))
    )
    (net (code "161") (name "unconnected-(U$3-VCC30-PadP$4)") (class "Default")
      (node (ref "U$3") (pin "P$4") (pinfunction "VCC30_P$4") (pintype "bidirectional"))
    )
    (net (code "162") (name "unconnected-(U3-B2-Pad6)") (class "Default")
      (node (ref "U3") (pin "6") (pinfunction "B2_6") (pintype "output"))
    )
    (net (code "163") (name "unconnected-(U5-B5-Pad11)") (class "Default")
      (node (ref "U5") (pin "11") (pinfunction "B5_11") (pintype "output"))
    )
    (net (code "164") (name "unconnected-(U5-B6-Pad10)") (class "Default")
      (node (ref "U5") (pin "10") (pinfunction "B6_10") (pintype "output"))
    )
  )
)
